# guitar_base.net
KiCad netlist of a schematic drawn in EAGLE
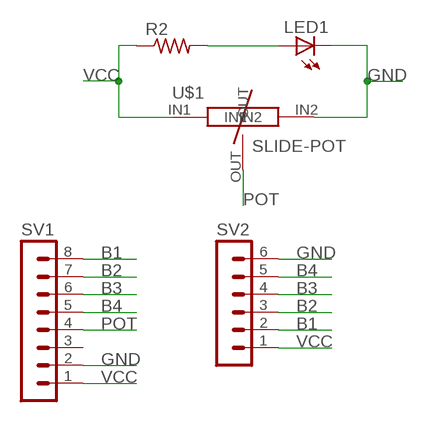
[diagram p0: schematic, sheet 1]

(export (version "E")
  (design (tool "Eeschema 10.0.6"))
  (components
    (comp (ref "LED1")
      (value "LED5MM")
      (footprint "eagle-import:LED5MM")
      (libsource (lib "eagle-import") (part "LED5MM"))
    )
    (comp (ref "R2")
      (value "R-US_0207/7")
      (footprint "eagle-import:0207_7")
      (libsource (lib "eagle-import") (part "R-US_0207/7"))
    )
    (comp (ref "SV1")
      (value "MA08-1")
      (footprint "eagle-import:MA08-1")
      (libsource (lib "eagle-import") (part "MA08-1"))
    )
    (comp (ref "SV2")
      (value "MA06-1")
      (footprint "eagle-import:MA06-1")
      (libsource (lib "eagle-import") (part "MA06-1"))
    )
    (comp (ref "U$1")
      (value "SLIDE-POT")
      (footprint "eagle-import:SLIDE-POT")
      (libsource (lib "eagle-import") (part "SLIDE-POT"))
    )
  )
  (nets
    (net (code "1") (name "/B1") (class "Default")
      (node (ref "SV1") (pin "8") (pinfunction "8_8") (pintype "passive"))
      (node (ref "SV2") (pin "2") (pinfunction "2_2") (pintype "passive"))
    )
    (net (code "2") (name "/B2") (class "Default")
      (node (ref "SV1") (pin "7") (pinfunction "7_7") (pintype "passive"))
      (node (ref "SV2") (pin "3") (pinfunction "3_3") (pintype "passive"))
    )
    (net (code "3") (name "/B3") (class "Default")
      (node (ref "SV1") (pin "6") (pinfunction "6_6") (pintype "passive"))
      (node (ref "SV2") (pin "4") (pinfunction "4_4") (pintype "passive"))
    )
    (net (code "4") (name "/B4") (class "Default")
      (node (ref "SV1") (pin "5") (pinfunction "5_5") (pintype "passive"))
      (node (ref "SV2") (pin "5") (pinfunction "5_5") (pintype "passive"))
    )
    (net (code "5") (name "/GND") (class "Default")
      (node (ref "LED1") (pin "K") (pinfunction "C_K") (pintype "passive"))
      (node (ref "SV1") (pin "2") (pinfunction "2_2") (pintype "passive"))
      (node (ref "SV2") (pin "6") (pinfunction "6_6") (pintype "passive"))
      (node (ref "U$1") (pin "IN2") (pinfunction "IN2_IN2") (pintype "bidirectional"))
    )
    (net (code "6") (name "/POT") (class "Default")
      (node (ref "SV1") (pin "4") (pinfunction "4_4") (pintype "passive"))
      (node (ref "U$1") (pin "OUT") (pinfunction "OUT_OUT") (pintype "bidirectional"))
    )
    (net (code "7") (name "/VCC") (class "Default")
      (node (ref "R2") (pin "1") (pinfunction "1_1") (pintype "passive"))
      (node (ref "SV1") (pin "1") (pinfunction "1_1") (pintype "passive"))
      (node (ref "SV2") (pin "1") (pinfunction "1_1") (pintype "passive"))
      (node (ref "U$1") (pin "IN1") (pinfunction "IN1_IN1") (pintype "bidirectional"))
    )
    (net (code "8") (name "Net-(LED1-PadA)") (class "Default")
      (node (ref "LED1") (pin "A") (pinfunction "A_A") (pintype "passive"))
      (node (ref "R2") (pin "2") (pinfunction "2_2") (pintype "passive"))
    )
    (net (code "9") (name "unconnected-(SV1-Pad3)") (class "Default")
      (node (ref "SV1") (pin "3") (pinfunction "3_3") (pintype "passive"))
    )
  )
)
